# HB-UNI-Sen-PM_v1.net
KiCad netlist of a schematic drawn in EAGLE
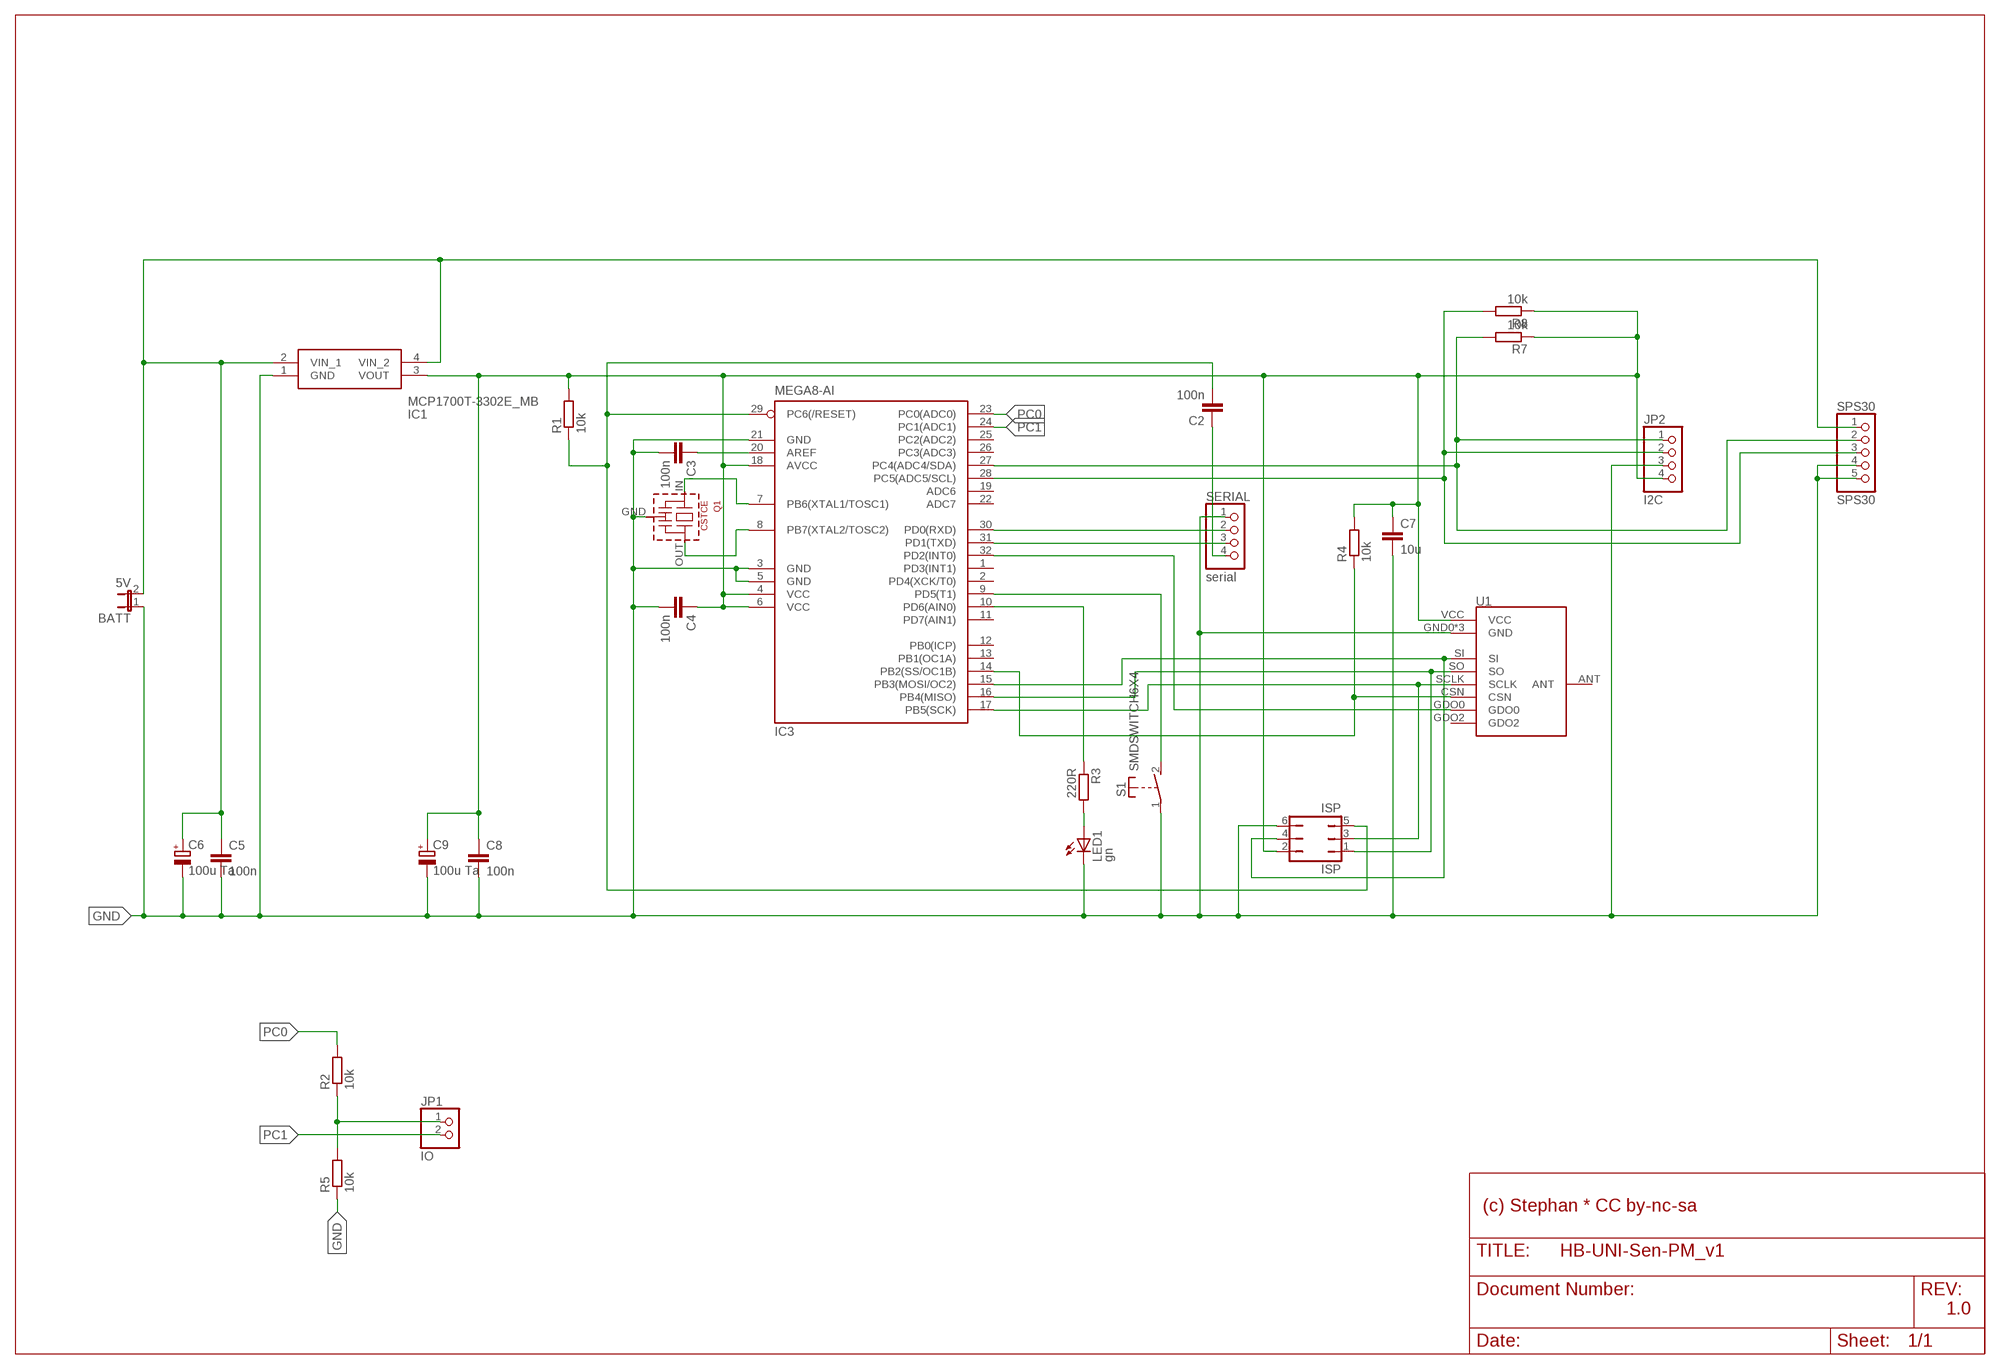
[diagram p0: schematic, sheet 1]

(export (version "E")
  (design (tool "Eeschema 10.0.6"))
  (components
    (comp (ref "BATT")
      (value "5V")
      (footprint "eagle-import:JP1")
      (libsource (lib "eagle-import") (part "JP1E"))
    )
    (comp (ref "C2")
      (value "100n")
      (footprint "eagle-import:C0805K")
      (libsource (lib "eagle-import") (part "C-EUC0805K"))
    )
    (comp (ref "C3")
      (value "100n")
      (footprint "eagle-import:C0805K")
      (libsource (lib "eagle-import") (part "C-EUC0805K"))
    )
    (comp (ref "C4")
      (value "100n")
      (footprint "eagle-import:C0805K")
      (libsource (lib "eagle-import") (part "C-EUC0805K"))
    )
    (comp (ref "C5")
      (value "100n")
      (footprint "eagle-import:C0805K")
      (libsource (lib "eagle-import") (part "C-EUC0805K"))
    )
    (comp (ref "C6")
      (value "100u Ta")
      (footprint "eagle-import:SANYO-OSCON_SMD_C6")
      (libsource (lib "eagle-import") (part "CPOL-EUSANYO_SMD_C6"))
    )
    (comp (ref "C7")
      (value "10u")
      (footprint "eagle-import:C0805K")
      (libsource (lib "eagle-import") (part "C-EUC0805K"))
    )
    (comp (ref "C8")
      (value "100n")
      (footprint "eagle-import:C0805K")
      (libsource (lib "eagle-import") (part "C-EUC0805K"))
    )
    (comp (ref "C9")
      (value "100u Ta")
      (footprint "eagle-import:SANYO-OSCON_SMD_C6")
      (libsource (lib "eagle-import") (part "CPOL-EUSANYO_SMD_C6"))
    )
    (comp (ref "IC1")
      (value "MCP1700T-3302E_MB")
      (footprint "eagle-import:MCP1700T-3302E_MB")
      (fields
        (field (name "ARROW_PART_NUMBER") "MCP1700T-3302E/MB")
        (field (name "MOUSER_PART_NUMBER") "579-MCP1700T3302E/MB")
      )
      (libsource (lib "eagle-import") (part "MCP1700T-3302E_MB"))
    )
    (comp (ref "IC3")
      (value "MEGA8-AI")
      (footprint "eagle-import:TQFP32-08")
      (fields (field (name "MPN") "ATMEGA8-16AU"))
      (libsource (lib "eagle-import") (part "MEGA8-AI"))
    )
    (comp (ref "ISP")
      (value "ISP")
      (footprint "eagle-import:JP3Q")
      (libsource (lib "eagle-import") (part "JP3Q"))
    )
    (comp (ref "JP1")
      (value "IO")
      (footprint "eagle-import:1X02")
      (libsource (lib "eagle-import") (part "PINHD-1X2"))
    )
    (comp (ref "JP2")
      (value "I2C")
      (footprint "eagle-import:1X04")
      (libsource (lib "eagle-import") (part "PINHD-1X4"))
    )
    (comp (ref "LED1")
      (value "gn")
      (footprint "eagle-import:CHIPLED_0805")
      (libsource (lib "eagle-import") (part "LEDCHIPLED_0805"))
    )
    (comp (ref "Q1")
      (value "CSTCE")
      (footprint "eagle-import:CSTCE")
      (libsource (lib "eagle-import") (part "CSTCE"))
    )
    (comp (ref "R1")
      (value "10k")
      (footprint "eagle-import:R0805W")
      (libsource (lib "eagle-import") (part "R-EU_R0805W"))
    )
    (comp (ref "R2")
      (value "10k")
      (footprint "eagle-import:R0805W")
      (libsource (lib "eagle-import") (part "R-EU_R0805W"))
    )
    (comp (ref "R3")
      (value "220R")
      (footprint "eagle-import:R0805W")
      (libsource (lib "eagle-import") (part "R-EU_R0805W"))
    )
    (comp (ref "R4")
      (value "10k")
      (footprint "eagle-import:R0805W")
      (libsource (lib "eagle-import") (part "R-EU_R0805W"))
    )
    (comp (ref "R5")
      (value "10k")
      (footprint "eagle-import:R0805W")
      (libsource (lib "eagle-import") (part "R-EU_R0805W"))
    )
    (comp (ref "R7")
      (value "10k")
      (footprint "eagle-import:R0805W")
      (libsource (lib "eagle-import") (part "R-EU_R0805W"))
    )
    (comp (ref "R8")
      (value "10k")
      (footprint "eagle-import:R0805W")
      (libsource (lib "eagle-import") (part "R-EU_R0805W"))
    )
    (comp (ref "S1")
      (value "SMDSWITCH6X4")
      (footprint "eagle-import:SMDSWITCH6X4")
      (libsource (lib "eagle-import") (part "SMDSWITCH6X4"))
    )
    (comp (ref "SERIAL")
      (value "serial")
      (footprint "eagle-import:1X04")
      (libsource (lib "eagle-import") (part "PINHD-1X4"))
    )
    (comp (ref "SPS30")
      (value "SPS30")
      (footprint "eagle-import:1X05")
      (libsource (lib "eagle-import") (part "PINHD-1X5"))
    )
    (comp (ref "U1")
      (value "CC1101SMD")
      (footprint "eagle-import:CC1101-SMD")
      (libsource (lib "eagle-import") (part "CC1101SMD"))
    )
  )
  (nets
    (net (code "1") (name "GND") (class "Default")
      (node (ref "BATT") (pin "1") (pinfunction "1_1") (pintype "passive"))
      (node (ref "C3") (pin "2") (pinfunction "2_2") (pintype "passive"))
      (node (ref "C4") (pin "2") (pinfunction "2_2") (pintype "passive"))
      (node (ref "C5") (pin "2") (pinfunction "2_2") (pintype "passive"))
      (node (ref "C6") (pin "-") (pinfunction "-_-") (pintype "passive"))
      (node (ref "C7") (pin "2") (pinfunction "2_2") (pintype "passive"))
      (node (ref "C8") (pin "2") (pinfunction "2_2") (pintype "passive"))
      (node (ref "C9") (pin "-") (pinfunction "-_-") (pintype "passive"))
      (node (ref "IC1") (pin "1") (pinfunction "GND_1") (pintype "power_in"))
      (node (ref "IC3") (pin "21") (pinfunction "GND_21") (pintype "power_in"))
      (node (ref "IC3") (pin "3") (pinfunction "GND_3") (pintype "power_in"))
      (node (ref "IC3") (pin "5") (pinfunction "GND_5") (pintype "power_in"))
      (node (ref "ISP") (pin "6") (pinfunction "6_6") (pintype "passive"))
      (node (ref "JP2") (pin "3") (pinfunction "3_3") (pintype "passive"))
      (node (ref "LED1") (pin "C") (pinfunction "C_C") (pintype "passive"))
      (node (ref "Q1") (pin "GND") (pinfunction "GND_GND") (pintype "power_in"))
      (node (ref "R5") (pin "1") (pinfunction "1_1") (pintype "passive"))
      (node (ref "S1") (pin "1") (pinfunction "P_1") (pintype "passive"))
      (node (ref "SERIAL") (pin "1") (pinfunction "1_1") (pintype "passive"))
      (node (ref "SPS30") (pin "4") (pinfunction "4_4") (pintype "passive"))
      (node (ref "SPS30") (pin "5") (pinfunction "5_5") (pintype "passive"))
      (node (ref "U1") (pin "GND0") (pinfunction "GND_GND0") (pintype "power_in"))
      (node (ref "U1") (pin "GND1") (pinfunction "GND_GND1") (pintype "power_in"))
      (node (ref "U1") (pin "GND2") (pinfunction "GND_GND2") (pintype "power_in"))
    )
    (net (code "2") (name "Net-(C2-Pad1)") (class "Default")
      (node (ref "C2") (pin "1") (pinfunction "1_1") (pintype "passive"))
      (node (ref "SERIAL") (pin "4") (pinfunction "4_4") (pintype "passive"))
    )
    (net (code "3") (name "Net-(IC1-VIN_1)") (class "Default")
      (node (ref "BATT") (pin "2") (pinfunction "2_2") (pintype "passive"))
      (node (ref "C5") (pin "1") (pinfunction "1_1") (pintype "passive"))
      (node (ref "C6") (pin "+") (pinfunction "+_+") (pintype "passive"))
      (node (ref "IC1") (pin "2") (pinfunction "VIN_1_2") (pintype "input"))
      (node (ref "IC1") (pin "4") (pinfunction "VIN_2_4") (pintype "bidirectional"))
      (node (ref "SPS30") (pin "1") (pinfunction "1_1") (pintype "passive"))
    )
    (net (code "4") (name "Net-(IC1-VOUT)") (class "Default")
      (node (ref "C4") (pin "1") (pinfunction "1_1") (pintype "passive"))
      (node (ref "C7") (pin "1") (pinfunction "1_1") (pintype "passive"))
      (node (ref "C8") (pin "1") (pinfunction "1_1") (pintype "passive"))
      (node (ref "C9") (pin "+") (pinfunction "+_+") (pintype "passive"))
      (node (ref "IC1") (pin "3") (pinfunction "VOUT_3") (pintype "output"))
      (node (ref "IC3") (pin "18") (pinfunction "AVCC_18") (pintype "power_in"))
      (node (ref "IC3") (pin "4") (pinfunction "VCC_4") (pintype "power_in"))
      (node (ref "IC3") (pin "6") (pinfunction "VCC_6") (pintype "power_in"))
      (node (ref "ISP") (pin "2") (pinfunction "2_2") (pintype "passive"))
      (node (ref "JP2") (pin "4") (pinfunction "4_4") (pintype "passive"))
      (node (ref "R1") (pin "2") (pinfunction "2_2") (pintype "passive"))
      (node (ref "R4") (pin "2") (pinfunction "2_2") (pintype "passive"))
      (node (ref "R7") (pin "1") (pinfunction "1_1") (pintype "passive"))
      (node (ref "R8") (pin "1") (pinfunction "1_1") (pintype "passive"))
      (node (ref "U1") (pin "VCC") (pinfunction "VCC_VCC") (pintype "power_in"))
    )
    (net (code "5") (name "Net-(IC3-AREF)") (class "Default")
      (node (ref "C3") (pin "1") (pinfunction "1_1") (pintype "passive"))
      (node (ref "IC3") (pin "20") (pinfunction "AREF_20") (pintype "passive"))
    )
    (net (code "6") (name "Net-(IC3-PB2(SS{slash}OC1B))") (class "Default")
      (node (ref "IC3") (pin "14") (pinfunction "PB2(SS/OC1B)_14") (pintype "bidirectional"))
      (node (ref "R4") (pin "1") (pinfunction "1_1") (pintype "passive"))
      (node (ref "U1") (pin "CSN") (pinfunction "CSN_CSN") (pintype "bidirectional"))
    )
    (net (code "7") (name "Net-(IC3-PB3(MOSI{slash}OC2))") (class "Default")
      (node (ref "IC3") (pin "15") (pinfunction "PB3(MOSI/OC2)_15") (pintype "bidirectional"))
      (node (ref "ISP") (pin "4") (pinfunction "4_4") (pintype "passive"))
      (node (ref "U1") (pin "SI") (pinfunction "SI_SI") (pintype "input"))
    )
    (net (code "8") (name "Net-(IC3-PB4(MISO))") (class "Default")
      (node (ref "IC3") (pin "16") (pinfunction "PB4(MISO)_16") (pintype "bidirectional"))
      (node (ref "ISP") (pin "1") (pinfunction "1_1") (pintype "passive"))
      (node (ref "U1") (pin "SO") (pinfunction "SO_SO") (pintype "output"))
    )
    (net (code "9") (name "Net-(IC3-PB5(SCK))") (class "Default")
      (node (ref "IC3") (pin "17") (pinfunction "PB5(SCK)_17") (pintype "bidirectional"))
      (node (ref "ISP") (pin "3") (pinfunction "3_3") (pintype "passive"))
      (node (ref "U1") (pin "SCLK") (pinfunction "SCLK_SCLK") (pintype "input"))
    )
    (net (code "10") (name "Net-(IC3-PB6(XTAL1{slash}TOSC1))") (class "Default")
      (node (ref "IC3") (pin "7") (pinfunction "PB6(XTAL1/TOSC1)_7") (pintype "bidirectional"))
      (node (ref "Q1") (pin "IN") (pinfunction "IN_IN") (pintype "input"))
    )
    (net (code "11") (name "Net-(IC3-PB7(XTAL2{slash}TOSC2))") (class "Default")
      (node (ref "IC3") (pin "8") (pinfunction "PB7(XTAL2/TOSC2)_8") (pintype "bidirectional"))
      (node (ref "Q1") (pin "OUT") (pinfunction "OUT_OUT") (pintype "output"))
    )
    (net (code "12") (name "Net-(IC3-PC4(ADC4{slash}SDA))") (class "Default")
      (node (ref "IC3") (pin "27") (pinfunction "PC4(ADC4/SDA)_27") (pintype "bidirectional"))
      (node (ref "JP2") (pin "1") (pinfunction "1_1") (pintype "passive"))
      (node (ref "R7") (pin "2") (pinfunction "2_2") (pintype "passive"))
      (node (ref "SPS30") (pin "2") (pinfunction "2_2") (pintype "passive"))
    )
    (net (code "13") (name "Net-(IC3-PC5(ADC5{slash}SCL))") (class "Default")
      (node (ref "IC3") (pin "28") (pinfunction "PC5(ADC5/SCL)_28") (pintype "bidirectional"))
      (node (ref "JP2") (pin "2") (pinfunction "2_2") (pintype "passive"))
      (node (ref "R8") (pin "2") (pinfunction "2_2") (pintype "passive"))
      (node (ref "SPS30") (pin "3") (pinfunction "3_3") (pintype "passive"))
    )
    (net (code "14") (name "Net-(IC3-PC6({slash}RESET))") (class "Default")
      (node (ref "C2") (pin "2") (pinfunction "2_2") (pintype "passive"))
      (node (ref "IC3") (pin "29") (pinfunction "PC6(/RESET)_29") (pintype "bidirectional"))
      (node (ref "ISP") (pin "5") (pinfunction "5_5") (pintype "passive"))
      (node (ref "R1") (pin "1") (pinfunction "1_1") (pintype "passive"))
    )
    (net (code "15") (name "Net-(IC3-PD0(RXD))") (class "Default")
      (node (ref "IC3") (pin "30") (pinfunction "PD0(RXD)_30") (pintype "bidirectional"))
      (node (ref "SERIAL") (pin "2") (pinfunction "2_2") (pintype "passive"))
    )
    (net (code "16") (name "Net-(IC3-PD1(TXD))") (class "Default")
      (node (ref "IC3") (pin "31") (pinfunction "PD1(TXD)_31") (pintype "bidirectional"))
      (node (ref "SERIAL") (pin "3") (pinfunction "3_3") (pintype "passive"))
    )
    (net (code "17") (name "Net-(IC3-PD2(INT0))") (class "Default")
      (node (ref "IC3") (pin "32") (pinfunction "PD2(INT0)_32") (pintype "bidirectional"))
      (node (ref "U1") (pin "GDO0") (pinfunction "GDO0_GDO0") (pintype "output"))
    )
    (net (code "18") (name "Net-(IC3-PD5(T1))") (class "Default")
      (node (ref "IC3") (pin "9") (pinfunction "PD5(T1)_9") (pintype "bidirectional"))
      (node (ref "S1") (pin "2") (pinfunction "S_2") (pintype "passive"))
    )
    (net (code "19") (name "Net-(IC3-PD6(AIN0))") (class "Default")
      (node (ref "IC3") (pin "10") (pinfunction "PD6(AIN0)_10") (pintype "bidirectional"))
      (node (ref "R3") (pin "1") (pinfunction "1_1") (pintype "passive"))
    )
    (net (code "20") (name "Net-(JP1-Pad1)") (class "Default")
      (node (ref "JP1") (pin "1") (pinfunction "1_1") (pintype "passive"))
      (node (ref "R2") (pin "1") (pinfunction "1_1") (pintype "passive"))
      (node (ref "R5") (pin "2") (pinfunction "2_2") (pintype "passive"))
    )
    (net (code "21") (name "Net-(LED1-PadA)") (class "Default")
      (node (ref "LED1") (pin "A") (pinfunction "A_A") (pintype "passive"))
      (node (ref "R3") (pin "2") (pinfunction "2_2") (pintype "passive"))
    )
    (net (code "22") (name "PC0") (class "Default")
      (node (ref "IC3") (pin "23") (pinfunction "PC0(ADC0)_23") (pintype "bidirectional"))
      (node (ref "R2") (pin "2") (pinfunction "2_2") (pintype "passive"))
    )
    (net (code "23") (name "PC1") (class "Default")
      (node (ref "IC3") (pin "24") (pinfunction "PC1(ADC1)_24") (pintype "bidirectional"))
      (node (ref "JP1") (pin "2") (pinfunction "2_2") (pintype "passive"))
    )
    (net (code "24") (name "unconnected-(IC3-ADC6-Pad19)") (class "Default")
      (node (ref "IC3") (pin "19") (pinfunction "ADC6_19") (pintype "bidirectional"))
    )
    (net (code "25") (name "unconnected-(IC3-ADC7-Pad22)") (class "Default")
      (node (ref "IC3") (pin "22") (pinfunction "ADC7_22") (pintype "bidirectional"))
    )
    (net (code "26") (name "unconnected-(IC3-PB0(ICP)-Pad12)") (class "Default")
      (node (ref "IC3") (pin "12") (pinfunction "PB0(ICP)_12") (pintype "bidirectional"))
    )
    (net (code "27") (name "unconnected-(IC3-PB1(OC1A)-Pad13)") (class "Default")
      (node (ref "IC3") (pin "13") (pinfunction "PB1(OC1A)_13") (pintype "bidirectional"))
    )
    (net (code "28") (name "unconnected-(IC3-PC2(ADC2)-Pad25)") (class "Default")
      (node (ref "IC3") (pin "25") (pinfunction "PC2(ADC2)_25") (pintype "bidirectional"))
    )
    (net (code "29") (name "unconnected-(IC3-PC3(ADC3)-Pad26)") (class "Default")
      (node (ref "IC3") (pin "26") (pinfunction "PC3(ADC3)_26") (pintype "bidirectional"))
    )
    (net (code "30") (name "unconnected-(IC3-PD3(INT1)-Pad1)") (class "Default")
      (node (ref "IC3") (pin "1") (pinfunction "PD3(INT1)_1") (pintype "bidirectional"))
    )
    (net (code "31") (name "unconnected-(IC3-PD4(XCK{slash}T0)-Pad2)") (class "Default")
      (node (ref "IC3") (pin "2") (pinfunction "PD4(XCK/T0)_2") (pintype "bidirectional"))
    )
    (net (code "32") (name "unconnected-(IC3-PD7(AIN1)-Pad11)") (class "Default")
      (node (ref "IC3") (pin "11") (pinfunction "PD7(AIN1)_11") (pintype "bidirectional"))
    )
    (net (code "33") (name "unconnected-(U1-PadANT)") (class "Default")
      (node (ref "U1") (pin "ANT") (pinfunction "ANT_ANT") (pintype "input"))
    )
    (net (code "34") (name "unconnected-(U1-PadGDO2)") (class "Default")
      (node (ref "U1") (pin "GDO2") (pinfunction "GDO2_GDO2") (pintype "output"))
    )
  )
)
